# Amp_op1.net
KiCad netlist of a schematic drawn in Altium Designer
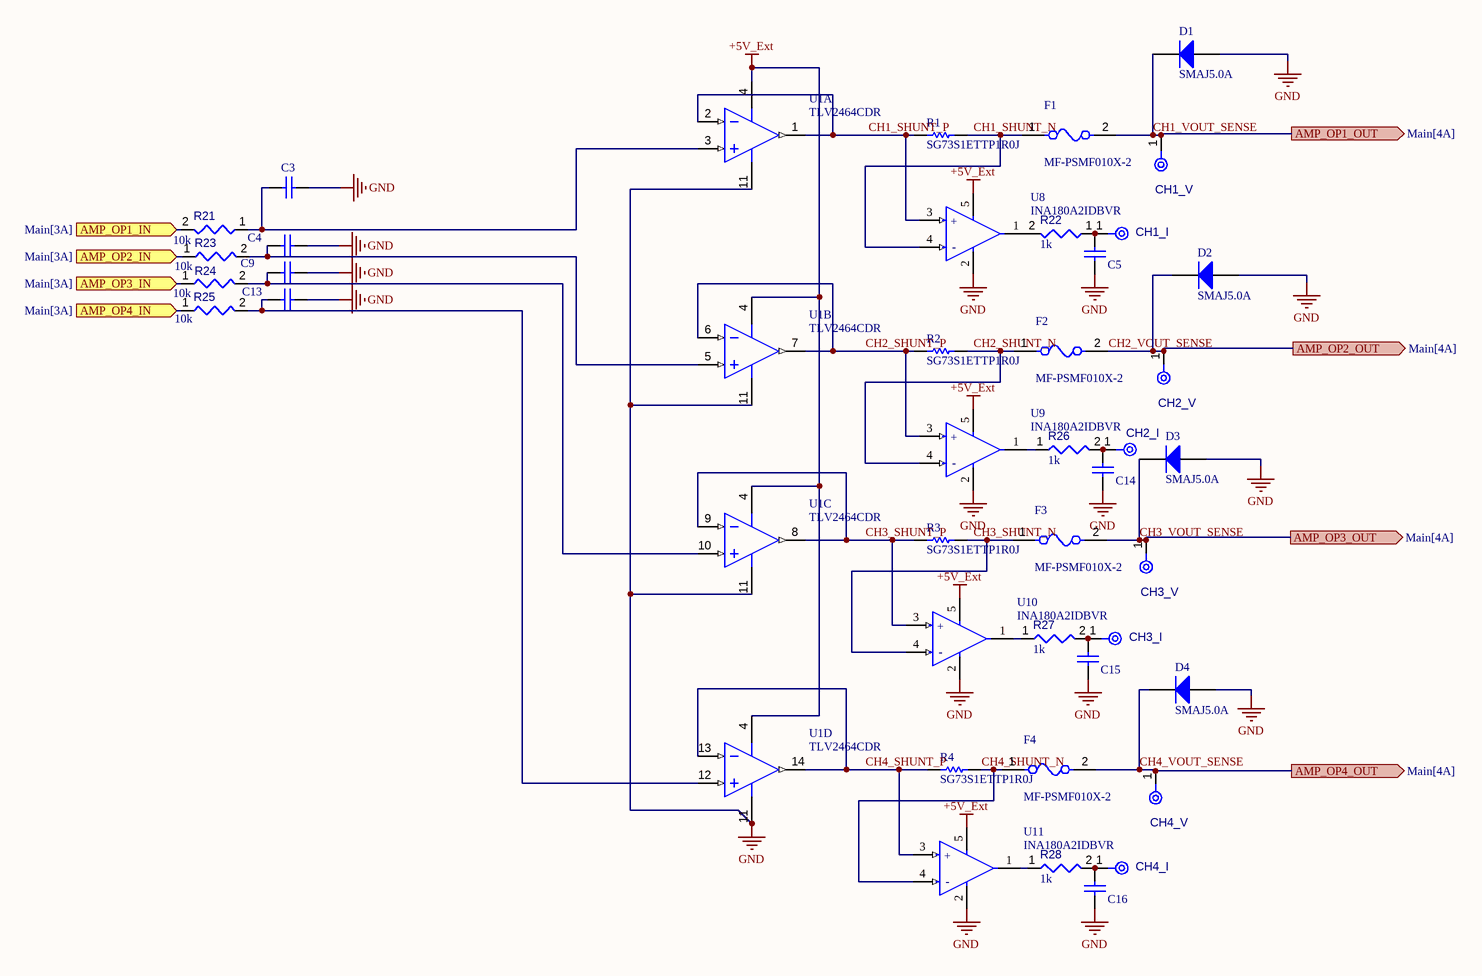
[diagram p0: Amp_op1.SchDoc]

(export (version "E")
  (design (tool "Eeschema 10.0.6"))
  (components
    (comp (ref "C3")
      (value "VJ0603Y104MXJCW1BC")
      (footprint "CAPC1608X95X40NL15T15")
      (fields (field (name "MANUFACTURER") "Vitramon"))
      (libsource (lib "Altium Content Vault") (part "CAP"))
    )
    (comp (ref "C4")
      (value "VJ0603Y104MXJCW1BC")
      (footprint "CAPC1608X95X40NL15T15")
      (fields (field (name "MANUFACTURER") "Vitramon"))
      (libsource (lib "Altium Content Vault") (part "CAP"))
    )
    (comp (ref "C5")
      (value "VJ0603Y104MXJCW1BC")
      (footprint "CAPC1608X95X40NL15T15")
      (fields (field (name "MANUFACTURER") "Vitramon"))
      (libsource (lib "Altium Content Vault") (part "CAP"))
    )
    (comp (ref "C9")
      (value "VJ0603Y104MXJCW1BC")
      (footprint "CAPC1608X95X40NL15T15")
      (fields (field (name "MANUFACTURER") "Vitramon"))
      (libsource (lib "Altium Content Vault") (part "CAP"))
    )
    (comp (ref "C13")
      (value "VJ0603Y104MXJCW1BC")
      (footprint "CAPC1608X95X40NL15T15")
      (fields (field (name "MANUFACTURER") "Vitramon"))
      (libsource (lib "Altium Content Vault") (part "CAP"))
    )
    (comp (ref "C14")
      (value "VJ0603Y104MXJCW1BC")
      (footprint "CAPC1608X95X40NL15T15")
      (fields (field (name "MANUFACTURER") "Vitramon"))
      (libsource (lib "Altium Content Vault") (part "CAP"))
    )
    (comp (ref "C15")
      (value "VJ0603Y104MXJCW1BC")
      (footprint "CAPC1608X95X40NL15T15")
      (fields (field (name "MANUFACTURER") "Vitramon"))
      (libsource (lib "Altium Content Vault") (part "CAP"))
    )
    (comp (ref "C16")
      (value "VJ0603Y104MXJCW1BC")
      (footprint "CAPC1608X95X40NL15T15")
      (fields (field (name "MANUFACTURER") "Vitramon"))
      (libsource (lib "Altium Content Vault") (part "CAP"))
    )
    (comp (ref "CH1_I")
      (value "TPAD6R")
      (footprint "TP06R")
      (description "0.6mm round")
      (libsource (lib "PCEIOT") (part "CMP-00028-00002-2"))
    )
    (comp (ref "CH1_V")
      (value "TPAD6R")
      (footprint "TP06R")
      (description "0.6mm round")
      (libsource (lib "PCEIOT") (part "CMP-00028-00002-2"))
    )
    (comp (ref "CH2_I")
      (value "TPAD6R")
      (footprint "TP06R")
      (description "0.6mm round")
      (libsource (lib "PCEIOT") (part "CMP-00028-00002-2"))
    )
    (comp (ref "CH2_V")
      (value "TPAD6R")
      (footprint "TP06R")
      (description "0.6mm round")
      (libsource (lib "PCEIOT") (part "CMP-00028-00002-2"))
    )
    (comp (ref "CH3_I")
      (value "TPAD6R")
      (footprint "TP06R")
      (description "0.6mm round")
      (libsource (lib "PCEIOT") (part "CMP-00028-00002-2"))
    )
    (comp (ref "CH3_V")
      (value "TPAD6R")
      (footprint "TP06R")
      (description "0.6mm round")
      (libsource (lib "PCEIOT") (part "CMP-00028-00002-2"))
    )
    (comp (ref "CH4_I")
      (value "TPAD6R")
      (footprint "TP06R")
      (description "0.6mm round")
      (libsource (lib "PCEIOT") (part "CMP-00028-00002-2"))
    )
    (comp (ref "CH4_V")
      (value "TPAD6R")
      (footprint "TP06R")
      (description "0.6mm round")
      (libsource (lib "PCEIOT") (part "CMP-00028-00002-2"))
    )
    (comp (ref "D1")
      (value "SMAJ5.0A")
      (footprint "BOUR-SMA-2_V")
      (fields (field (name "MANUFACTURER") "Bourns"))
      (libsource (lib "Altium Content Vault") (part "D-AK-2"))
    )
    (comp (ref "D2")
      (value "SMAJ5.0A")
      (footprint "BOUR-SMA-2_V")
      (fields (field (name "MANUFACTURER") "Bourns"))
      (libsource (lib "Altium Content Vault") (part "D-AK-2"))
    )
    (comp (ref "D3")
      (value "SMAJ5.0A")
      (footprint "BOUR-SMA-2_V")
      (fields (field (name "MANUFACTURER") "Bourns"))
      (libsource (lib "Altium Content Vault") (part "D-AK-2"))
    )
    (comp (ref "D4")
      (value "SMAJ5.0A")
      (footprint "BOUR-SMA-2_V")
      (fields (field (name "MANUFACTURER") "Bourns"))
      (libsource (lib "Altium Content Vault") (part "D-AK-2"))
    )
    (comp (ref "F1")
      (value "MF-PSMF010X-2")
      (footprint "FP-MF-PSMF-MFG")
      (description "PTC RESET FUSE 15V 100MA 0805")
      (fields
        (field (name "OCTOPART") "https://octopart.com/mf-psmf010x-2-bourns-7483441")
        (field (name "MANUFACTURER") "Bourns Inc.")
      )
      (libsource (lib "Altium Content Vault") (part "5bcf9b9f640e542cf0359d10258e979"))
    )
    (comp (ref "F2")
      (value "MF-PSMF010X-2")
      (footprint "FP-MF-PSMF-MFG")
      (description "PTC RESET FUSE 15V 100MA 0805")
      (fields
        (field (name "OCTOPART") "https://octopart.com/mf-psmf010x-2-bourns-7483441")
        (field (name "MANUFACTURER") "Bourns Inc.")
      )
      (libsource (lib "Altium Content Vault") (part "5bcf9b9f640e542cf0359d10258e979"))
    )
    (comp (ref "F3")
      (value "MF-PSMF010X-2")
      (footprint "FP-MF-PSMF-MFG")
      (description "PTC RESET FUSE 15V 100MA 0805")
      (fields
        (field (name "OCTOPART") "https://octopart.com/mf-psmf010x-2-bourns-7483441")
        (field (name "MANUFACTURER") "Bourns Inc.")
      )
      (libsource (lib "Altium Content Vault") (part "5bcf9b9f640e542cf0359d10258e979"))
    )
    (comp (ref "F4")
      (value "MF-PSMF010X-2")
      (footprint "FP-MF-PSMF-MFG")
      (description "PTC RESET FUSE 15V 100MA 0805")
      (fields
        (field (name "OCTOPART") "https://octopart.com/mf-psmf010x-2-bourns-7483441")
        (field (name "MANUFACTURER") "Bourns Inc.")
      )
      (libsource (lib "Altium Content Vault") (part "5bcf9b9f640e542cf0359d10258e979"))
    )
    (comp (ref "R1")
      (value "SG73S1ETTP1R0J")
      (footprint "RESC1005X40X25LL10T10")
      (fields (field (name "MANUFACTURER") "KOA Speer"))
      (libsource (lib "Altium Content Vault") (part "RES"))
    )
    (comp (ref "R2")
      (value "SG73S1ETTP1R0J")
      (footprint "RESC1005X40X25LL10T10")
      (fields (field (name "MANUFACTURER") "KOA Speer"))
      (libsource (lib "Altium Content Vault") (part "RES"))
    )
    (comp (ref "R3")
      (value "SG73S1ETTP1R0J")
      (footprint "RESC1005X40X25LL10T10")
      (fields (field (name "MANUFACTURER") "KOA Speer"))
      (libsource (lib "Altium Content Vault") (part "RES"))
    )
    (comp (ref "R4")
      (value "SG73S1ETTP1R0J")
      (footprint "RESC1005X40X25LL10T10")
      (fields (field (name "MANUFACTURER") "KOA Speer"))
      (libsource (lib "Altium Content Vault") (part "RES"))
    )
    (comp (ref "R21")
      (value "10k")
      (footprint "RESC0603(1608)_L")
      (description "Chip Resistor, 10 KOhm, +/- 1%, 01 W, -55 to 155 degC, 0603 (1608 Metric)")
      (fields (field (name "POWER") "100mW") (field (name "TOLERANCE") "1%"))
      (libsource (lib "PCEIOT") (part "CMP-009-00017-7"))
    )
    (comp (ref "R22")
      (value "1k")
      (footprint "RESC0603(1608)_L")
      (description "Chip Resistor, 1 KOhm, +/-1%, 0.1 W, -55 to 155 degC, 0603 (1608 Metric)")
      (fields (field (name "POWER") "100mW") (field (name "TOLERANCE") "1%"))
      (libsource (lib "PCEIOT") (part "CMP-009-00014-6"))
    )
    (comp (ref "R23")
      (value "10k")
      (footprint "RESC0603(1608)_L")
      (description "Chip Resistor, 10 KOhm, +/- 1%, 01 W, -55 to 155 degC, 0603 (1608 Metric)")
      (fields (field (name "POWER") "100mW") (field (name "TOLERANCE") "1%"))
      (libsource (lib "PCEIOT") (part "CMP-009-00017-7"))
    )
    (comp (ref "R24")
      (value "10k")
      (footprint "RESC0603(1608)_L")
      (description "Chip Resistor, 10 KOhm, +/- 1%, 01 W, -55 to 155 degC, 0603 (1608 Metric)")
      (fields (field (name "POWER") "100mW") (field (name "TOLERANCE") "1%"))
      (libsource (lib "PCEIOT") (part "CMP-009-00017-7"))
    )
    (comp (ref "R25")
      (value "10k")
      (footprint "RESC0603(1608)_L")
      (description "Chip Resistor, 10 KOhm, +/- 1%, 01 W, -55 to 155 degC, 0603 (1608 Metric)")
      (fields (field (name "POWER") "100mW") (field (name "TOLERANCE") "1%"))
      (libsource (lib "PCEIOT") (part "CMP-009-00017-7"))
    )
    (comp (ref "R26")
      (value "1k")
      (footprint "RESC0603(1608)_L")
      (description "Chip Resistor, 1 KOhm, +/-1%, 0.1 W, -55 to 155 degC, 0603 (1608 Metric)")
      (fields (field (name "POWER") "100mW") (field (name "TOLERANCE") "1%"))
      (libsource (lib "PCEIOT") (part "CMP-009-00014-6"))
    )
    (comp (ref "R27")
      (value "1k")
      (footprint "RESC0603(1608)_L")
      (description "Chip Resistor, 1 KOhm, +/-1%, 0.1 W, -55 to 155 degC, 0603 (1608 Metric)")
      (fields (field (name "POWER") "100mW") (field (name "TOLERANCE") "1%"))
      (libsource (lib "PCEIOT") (part "CMP-009-00014-6"))
    )
    (comp (ref "R28")
      (value "1k")
      (footprint "RESC0603(1608)_L")
      (description "Chip Resistor, 1 KOhm, +/-1%, 0.1 W, -55 to 155 degC, 0603 (1608 Metric)")
      (fields (field (name "POWER") "100mW") (field (name "TOLERANCE") "1%"))
      (libsource (lib "PCEIOT") (part "CMP-009-00014-6"))
    )
    (comp (ref "U1")
      (value "TLV2464CDR")
      (footprint "D0014A_N")
      (fields (field (name "MANUFACTURER") "Texas Instruments"))
      (libsource (lib "Altium Content Vault") (part "TI-TLV2464X-XX14"))
    )
    (comp (ref "U8")
      (value "INA180A2IDBVR")
      (footprint "FP-DBV0005A-MFG")
      (description "IC CURR SENSE 1 CIRCUIT SOT23-5")
      (libsource (lib "Altium Content Vault") (part "0a55cf1a948ad01a3239aec1b7efad0"))
    )
    (comp (ref "U9")
      (value "INA180A2IDBVR")
      (footprint "FP-DBV0005A-MFG")
      (description "IC CURR SENSE 1 CIRCUIT SOT23-5")
      (libsource (lib "Altium Content Vault") (part "0a55cf1a948ad01a3239aec1b7efad0"))
    )
    (comp (ref "U10")
      (value "INA180A2IDBVR")
      (footprint "FP-DBV0005A-MFG")
      (description "IC CURR SENSE 1 CIRCUIT SOT23-5")
      (libsource (lib "Altium Content Vault") (part "0a55cf1a948ad01a3239aec1b7efad0"))
    )
    (comp (ref "U11")
      (value "INA180A2IDBVR")
      (footprint "FP-DBV0005A-MFG")
      (description "IC CURR SENSE 1 CIRCUIT SOT23-5")
      (libsource (lib "Altium Content Vault") (part "0a55cf1a948ad01a3239aec1b7efad0"))
    )
  )
  (nets
    (net (code "1") (name "+5V_Ext") (class "Default")
      (node (ref "U1") (pin "4") (pinfunction "VDD+_4") (pintype "power_in"))
      (node (ref "U10") (pin "5") (pinfunction "VS_5") (pintype "power_in"))
      (node (ref "U11") (pin "5") (pinfunction "VS_5") (pintype "power_in"))
      (node (ref "U8") (pin "5") (pinfunction "VS_5") (pintype "power_in"))
      (node (ref "U9") (pin "5") (pinfunction "VS_5") (pintype "power_in"))
    )
    (net (code "2") (name "/AMP_OP1_IN") (class "Default")
      (node (ref "R21") (pin "2") (pinfunction "2_2") (pintype "passive"))
    )
    (net (code "3") (name "/AMP_OP2_IN") (class "Default")
      (node (ref "R23") (pin "1") (pinfunction "1_1") (pintype "passive"))
    )
    (net (code "4") (name "/AMP_OP3_IN") (class "Default")
      (node (ref "R24") (pin "1") (pinfunction "1_1") (pintype "passive"))
    )
    (net (code "5") (name "/AMP_OP4_IN") (class "Default")
      (node (ref "R25") (pin "1") (pinfunction "1_1") (pintype "passive"))
    )
    (net (code "6") (name "/CH1_SHUNT_N") (class "Default")
      (node (ref "F1") (pin "1") (pinfunction "1_1") (pintype "passive"))
      (node (ref "R1") (pin "2") (pinfunction "2_2") (pintype "passive"))
      (node (ref "U8") (pin "4") (pinfunction "IN-_4") (pintype "input"))
    )
    (net (code "7") (name "/CH1_SHUNT_P") (class "Default")
      (node (ref "R1") (pin "1") (pinfunction "1_1") (pintype "passive"))
      (node (ref "U1") (pin "1") (pinfunction "OUT1_1") (pintype "output"))
      (node (ref "U1") (pin "2") (pinfunction "IN1-_2") (pintype "input"))
      (node (ref "U8") (pin "3") (pinfunction "IN+_3") (pintype "input"))
    )
    (net (code "8") (name "/CH1_VOUT_SENSE") (class "Default")
      (node (ref "CH1_V") (pin "1") (pinfunction "TP_1") (pintype "passive"))
      (node (ref "D1") (pin "2") (pinfunction "K_2") (pintype "passive"))
      (node (ref "F1") (pin "2") (pinfunction "2_2") (pintype "passive"))
    )
    (net (code "9") (name "/CH2_SHUNT_N") (class "Default")
      (node (ref "F2") (pin "1") (pinfunction "1_1") (pintype "passive"))
      (node (ref "R2") (pin "2") (pinfunction "2_2") (pintype "passive"))
      (node (ref "U9") (pin "4") (pinfunction "IN-_4") (pintype "input"))
    )
    (net (code "10") (name "/CH2_SHUNT_P") (class "Default")
      (node (ref "R2") (pin "1") (pinfunction "1_1") (pintype "passive"))
      (node (ref "U1") (pin "6") (pinfunction "IN2-_6") (pintype "input"))
      (node (ref "U1") (pin "7") (pinfunction "OUT2_7") (pintype "output"))
      (node (ref "U9") (pin "3") (pinfunction "IN+_3") (pintype "input"))
    )
    (net (code "11") (name "/CH2_VOUT_SENSE") (class "Default")
      (node (ref "CH2_V") (pin "1") (pinfunction "TP_1") (pintype "passive"))
      (node (ref "D2") (pin "2") (pinfunction "K_2") (pintype "passive"))
      (node (ref "F2") (pin "2") (pinfunction "2_2") (pintype "passive"))
    )
    (net (code "12") (name "/CH3_SHUNT_N") (class "Default")
      (node (ref "F3") (pin "1") (pinfunction "1_1") (pintype "passive"))
      (node (ref "R3") (pin "2") (pinfunction "2_2") (pintype "passive"))
      (node (ref "U10") (pin "4") (pinfunction "IN-_4") (pintype "input"))
    )
    (net (code "13") (name "/CH3_SHUNT_P") (class "Default")
      (node (ref "R3") (pin "1") (pinfunction "1_1") (pintype "passive"))
      (node (ref "U1") (pin "8") (pinfunction "OUT3_8") (pintype "output"))
      (node (ref "U1") (pin "9") (pinfunction "IN3-_9") (pintype "input"))
      (node (ref "U10") (pin "3") (pinfunction "IN+_3") (pintype "input"))
    )
    (net (code "14") (name "/CH3_VOUT_SENSE") (class "Default")
      (node (ref "CH3_V") (pin "1") (pinfunction "TP_1") (pintype "passive"))
      (node (ref "D3") (pin "2") (pinfunction "K_2") (pintype "passive"))
      (node (ref "F3") (pin "2") (pinfunction "2_2") (pintype "passive"))
    )
    (net (code "15") (name "/CH4_SHUNT_N") (class "Default")
      (node (ref "F4") (pin "1") (pinfunction "1_1") (pintype "passive"))
      (node (ref "R4") (pin "2") (pinfunction "2_2") (pintype "passive"))
      (node (ref "U11") (pin "4") (pinfunction "IN-_4") (pintype "input"))
    )
    (net (code "16") (name "/CH4_SHUNT_P") (class "Default")
      (node (ref "R4") (pin "1") (pinfunction "1_1") (pintype "passive"))
      (node (ref "U1") (pin "13") (pinfunction "IN4-_13") (pintype "input"))
      (node (ref "U1") (pin "14") (pinfunction "OUT4_14") (pintype "output"))
      (node (ref "U11") (pin "3") (pinfunction "IN+_3") (pintype "input"))
    )
    (net (code "17") (name "/CH4_VOUT_SENSE") (class "Default")
      (node (ref "CH4_V") (pin "1") (pinfunction "TP_1") (pintype "passive"))
      (node (ref "D4") (pin "2") (pinfunction "K_2") (pintype "passive"))
      (node (ref "F4") (pin "2") (pinfunction "2_2") (pintype "passive"))
    )
    (net (code "18") (name "GND") (class "Default")
      (node (ref "C13") (pin "2") (pinfunction "2_2") (pintype "passive"))
      (node (ref "C14") (pin "2") (pinfunction "2_2") (pintype "passive"))
      (node (ref "C15") (pin "2") (pinfunction "2_2") (pintype "passive"))
      (node (ref "C16") (pin "2") (pinfunction "2_2") (pintype "passive"))
      (node (ref "C3") (pin "2") (pinfunction "2_2") (pintype "passive"))
      (node (ref "C4") (pin "2") (pinfunction "2_2") (pintype "passive"))
      (node (ref "C5") (pin "1") (pinfunction "1_1") (pintype "passive"))
      (node (ref "C9") (pin "2") (pinfunction "2_2") (pintype "passive"))
      (node (ref "D1") (pin "1") (pinfunction "A_1") (pintype "passive"))
      (node (ref "D2") (pin "1") (pinfunction "A_1") (pintype "passive"))
      (node (ref "D3") (pin "1") (pinfunction "A_1") (pintype "passive"))
      (node (ref "D4") (pin "1") (pinfunction "A_1") (pintype "passive"))
      (node (ref "U1") (pin "11") (pinfunction "GND_11") (pintype "power_in"))
      (node (ref "U10") (pin "2") (pinfunction "GND_2") (pintype "power_in"))
      (node (ref "U11") (pin "2") (pinfunction "GND_2") (pintype "power_in"))
      (node (ref "U8") (pin "2") (pinfunction "GND_2") (pintype "power_in"))
      (node (ref "U9") (pin "2") (pinfunction "GND_2") (pintype "power_in"))
    )
    (net (code "19") (name "Net-(CH1_I-TP)") (class "Default")
      (node (ref "C5") (pin "2") (pinfunction "2_2") (pintype "passive"))
      (node (ref "CH1_I") (pin "1") (pinfunction "TP_1") (pintype "passive"))
      (node (ref "R22") (pin "1") (pinfunction "1_1") (pintype "passive"))
    )
    (net (code "20") (name "Net-(CH2_I-TP)") (class "Default")
      (node (ref "C14") (pin "1") (pinfunction "1_1") (pintype "passive"))
      (node (ref "CH2_I") (pin "1") (pinfunction "TP_1") (pintype "passive"))
      (node (ref "R26") (pin "2") (pinfunction "2_2") (pintype "passive"))
    )
    (net (code "21") (name "Net-(CH3_I-TP)") (class "Default")
      (node (ref "C15") (pin "1") (pinfunction "1_1") (pintype "passive"))
      (node (ref "CH3_I") (pin "1") (pinfunction "TP_1") (pintype "passive"))
      (node (ref "R27") (pin "2") (pinfunction "2_2") (pintype "passive"))
    )
    (net (code "22") (name "Net-(CH4_I-TP)") (class "Default")
      (node (ref "C16") (pin "1") (pinfunction "1_1") (pintype "passive"))
      (node (ref "CH4_I") (pin "1") (pinfunction "TP_1") (pintype "passive"))
      (node (ref "R28") (pin "2") (pinfunction "2_2") (pintype "passive"))
    )
    (net (code "23") (name "Net-(U1A-IN1+)") (class "Default")
      (node (ref "C3") (pin "1") (pinfunction "1_1") (pintype "passive"))
      (node (ref "R21") (pin "1") (pinfunction "1_1") (pintype "passive"))
      (node (ref "U1") (pin "3") (pinfunction "IN1+_3") (pintype "input"))
    )
    (net (code "24") (name "Net-(U1B-IN2+)") (class "Default")
      (node (ref "C4") (pin "1") (pinfunction "1_1") (pintype "passive"))
      (node (ref "R23") (pin "2") (pinfunction "2_2") (pintype "passive"))
      (node (ref "U1") (pin "5") (pinfunction "IN2+_5") (pintype "input"))
    )
    (net (code "25") (name "Net-(U1C-IN3+)") (class "Default")
      (node (ref "C9") (pin "1") (pinfunction "1_1") (pintype "passive"))
      (node (ref "R24") (pin "2") (pinfunction "2_2") (pintype "passive"))
      (node (ref "U1") (pin "10") (pinfunction "IN3+_10") (pintype "input"))
    )
    (net (code "26") (name "Net-(U1D-IN4+)") (class "Default")
      (node (ref "C13") (pin "1") (pinfunction "1_1") (pintype "passive"))
      (node (ref "R25") (pin "2") (pinfunction "2_2") (pintype "passive"))
      (node (ref "U1") (pin "12") (pinfunction "IN4+_12") (pintype "input"))
    )
    (net (code "27") (name "Net-(U8-OUT)") (class "Default")
      (node (ref "R22") (pin "2") (pinfunction "2_2") (pintype "passive"))
      (node (ref "U8") (pin "1") (pinfunction "OUT_1") (pintype "passive"))
    )
    (net (code "28") (name "Net-(U9-OUT)") (class "Default")
      (node (ref "R26") (pin "1") (pinfunction "1_1") (pintype "passive"))
      (node (ref "U9") (pin "1") (pinfunction "OUT_1") (pintype "passive"))
    )
    (net (code "29") (name "Net-(U10-OUT)") (class "Default")
      (node (ref "R27") (pin "1") (pinfunction "1_1") (pintype "passive"))
      (node (ref "U10") (pin "1") (pinfunction "OUT_1") (pintype "passive"))
    )
    (net (code "30") (name "Net-(U11-OUT)") (class "Default")
      (node (ref "R28") (pin "1") (pinfunction "1_1") (pintype "passive"))
      (node (ref "U11") (pin "1") (pinfunction "OUT_1") (pintype "passive"))
    )
  )
)
